# SAD_1_0.net
KiCad netlist of a schematic drawn in EAGLE
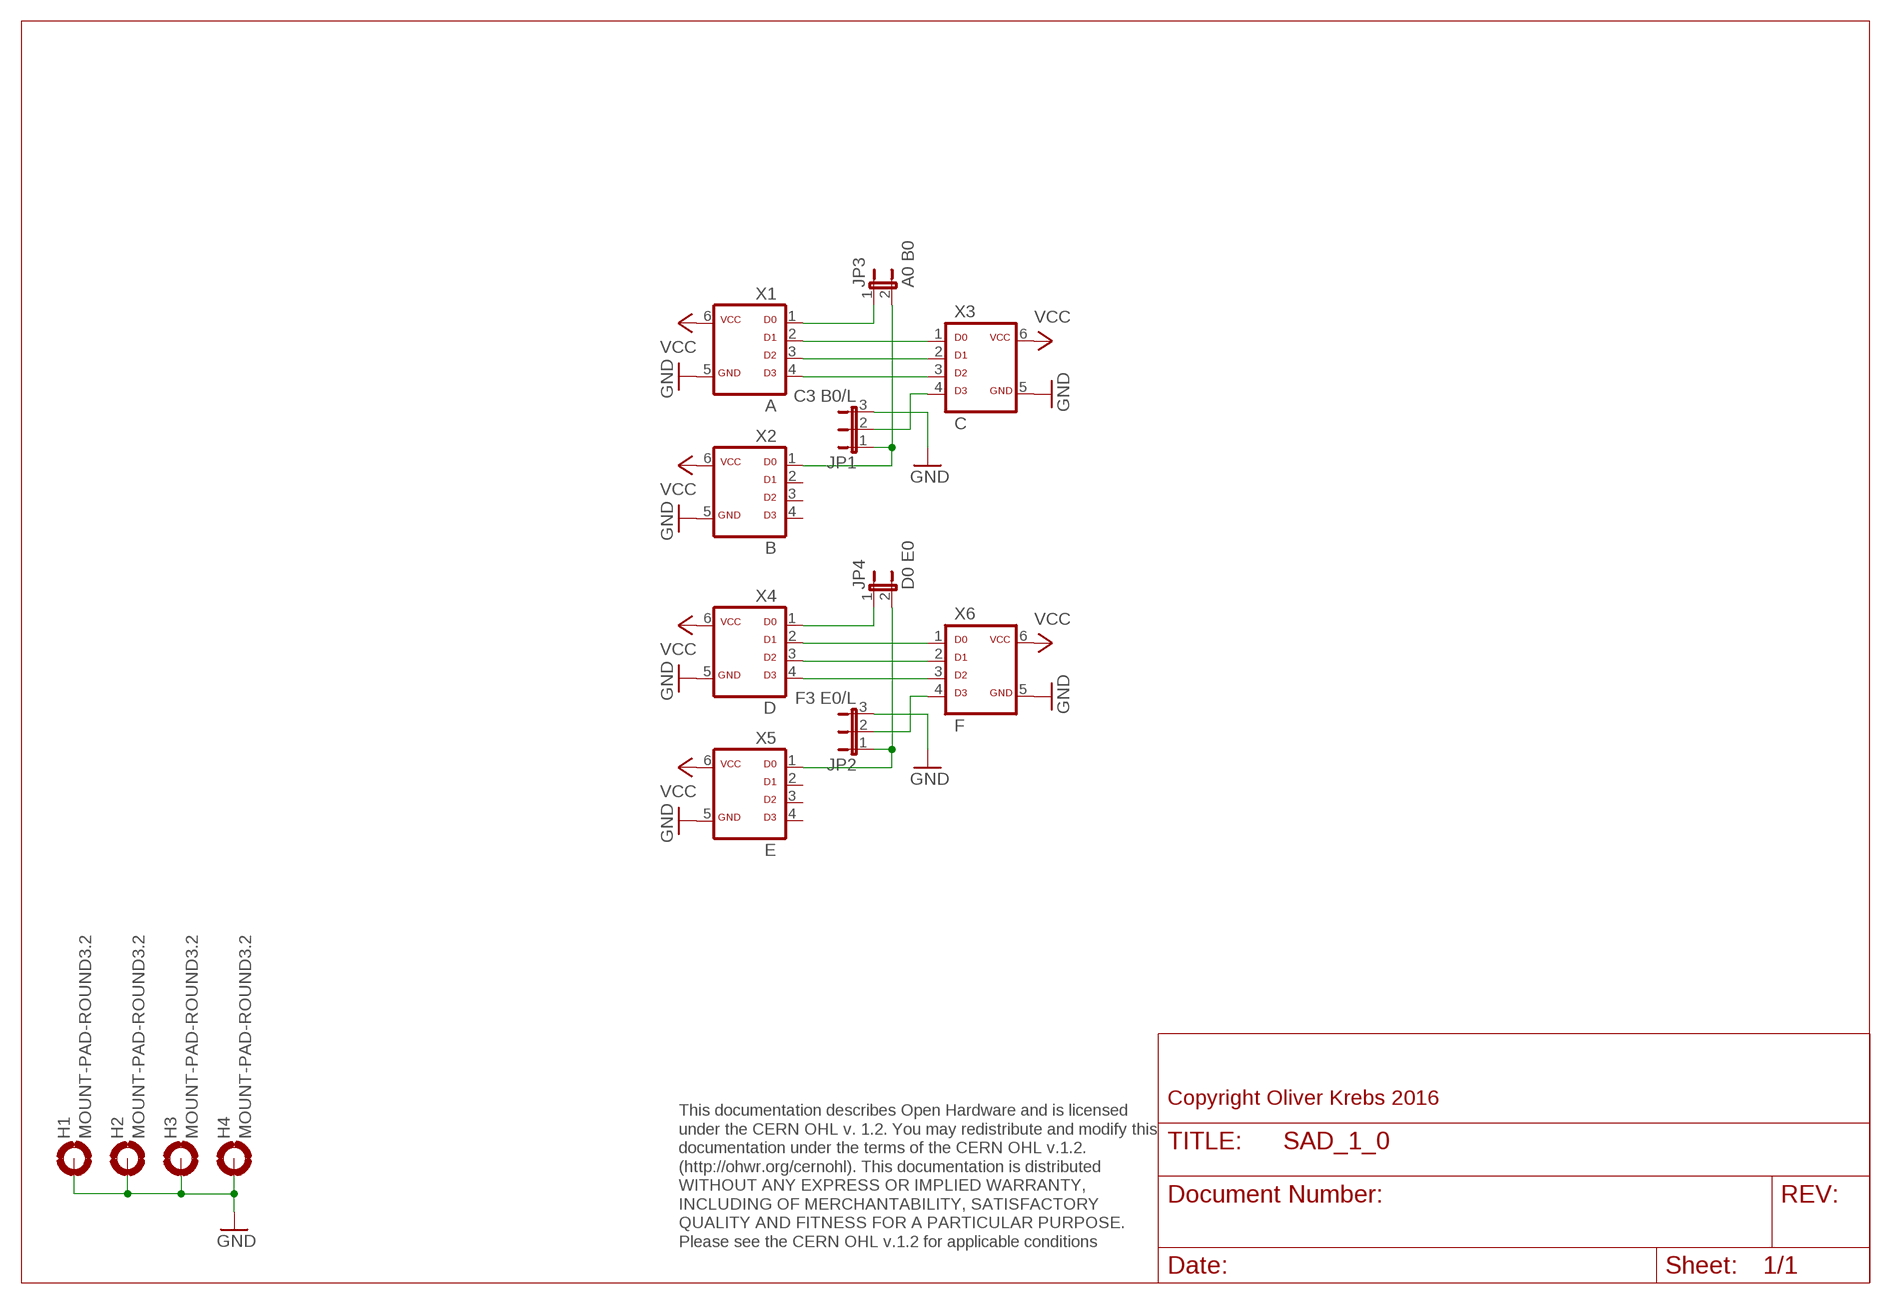
[diagram p0: schematic, sheet 1]

(export (version "E")
  (design (tool "Eeschema 10.0.6"))
  (components
    (comp (ref "H1")
      (value "MOUNT-PAD-ROUND3.2")
      (footprint "eagle-import:3,2-PAD")
      (libsource (lib "eagle-import") (part "MOUNT-PAD-ROUND3.2"))
    )
    (comp (ref "H2")
      (value "MOUNT-PAD-ROUND3.2")
      (footprint "eagle-import:3,2-PAD")
      (libsource (lib "eagle-import") (part "MOUNT-PAD-ROUND3.2"))
    )
    (comp (ref "H3")
      (value "MOUNT-PAD-ROUND3.2")
      (footprint "eagle-import:3,2-PAD")
      (libsource (lib "eagle-import") (part "MOUNT-PAD-ROUND3.2"))
    )
    (comp (ref "H4")
      (value "MOUNT-PAD-ROUND3.2")
      (footprint "eagle-import:3,2-PAD")
      (libsource (lib "eagle-import") (part "MOUNT-PAD-ROUND3.2"))
    )
    (comp (ref "JP1")
      (value "C3 B0/L")
      (footprint "eagle-import:JP2")
      (libsource (lib "eagle-import") (part "JP2E"))
    )
    (comp (ref "JP2")
      (value "F3 E0/L")
      (footprint "eagle-import:JP2")
      (libsource (lib "eagle-import") (part "JP2E"))
    )
    (comp (ref "JP3")
      (value "A0 B0")
      (footprint "eagle-import:JP1")
      (libsource (lib "eagle-import") (part "JP1E"))
    )
    (comp (ref "JP4")
      (value "D0 E0")
      (footprint "eagle-import:JP1")
      (libsource (lib "eagle-import") (part "JP1E"))
    )
    (comp (ref "X1")
      (value "A")
      (footprint "eagle-import:ML-6")
      (libsource (lib "eagle-import") (part "ML6D"))
    )
    (comp (ref "X2")
      (value "B")
      (footprint "eagle-import:ML-6")
      (libsource (lib "eagle-import") (part "ML6D"))
    )
    (comp (ref "X3")
      (value "C")
      (footprint "eagle-import:ML-6")
      (libsource (lib "eagle-import") (part "ML6D"))
    )
    (comp (ref "X4")
      (value "D")
      (footprint "eagle-import:ML-6")
      (libsource (lib "eagle-import") (part "ML6D"))
    )
    (comp (ref "X5")
      (value "E")
      (footprint "eagle-import:ML-6")
      (libsource (lib "eagle-import") (part "ML6D"))
    )
    (comp (ref "X6")
      (value "F")
      (footprint "eagle-import:ML-6")
      (libsource (lib "eagle-import") (part "ML6D"))
    )
  )
  (nets
    (net (code "1") (name "GND") (class "Default")
      (node (ref "H1") (pin "B3,2") (pinfunction "MOUNT_B3,2") (pintype "passive"))
      (node (ref "H2") (pin "B3,2") (pinfunction "MOUNT_B3,2") (pintype "passive"))
      (node (ref "H3") (pin "B3,2") (pinfunction "MOUNT_B3,2") (pintype "passive"))
      (node (ref "H4") (pin "B3,2") (pinfunction "MOUNT_B3,2") (pintype "passive"))
      (node (ref "JP1") (pin "3") (pinfunction "3_3") (pintype "passive"))
      (node (ref "JP2") (pin "3") (pinfunction "3_3") (pintype "passive"))
      (node (ref "X1") (pin "5") (pinfunction "5_5") (pintype "passive"))
      (node (ref "X2") (pin "5") (pinfunction "5_5") (pintype "passive"))
      (node (ref "X3") (pin "5") (pinfunction "5_5") (pintype "passive"))
      (node (ref "X4") (pin "5") (pinfunction "5_5") (pintype "passive"))
      (node (ref "X5") (pin "5") (pinfunction "5_5") (pintype "passive"))
      (node (ref "X6") (pin "5") (pinfunction "5_5") (pintype "passive"))
    )
    (net (code "2") (name "Net-(JP1-Pad1)") (class "Default")
      (node (ref "JP1") (pin "1") (pinfunction "1_1") (pintype "passive"))
      (node (ref "JP3") (pin "2") (pinfunction "2_2") (pintype "passive"))
      (node (ref "X2") (pin "1") (pinfunction "1_1") (pintype "passive"))
    )
    (net (code "3") (name "Net-(JP1-Pad2)") (class "Default")
      (node (ref "JP1") (pin "2") (pinfunction "2_2") (pintype "passive"))
      (node (ref "X3") (pin "4") (pinfunction "4_4") (pintype "passive"))
    )
    (net (code "4") (name "Net-(JP2-Pad1)") (class "Default")
      (node (ref "JP2") (pin "1") (pinfunction "1_1") (pintype "passive"))
      (node (ref "JP4") (pin "2") (pinfunction "2_2") (pintype "passive"))
      (node (ref "X5") (pin "1") (pinfunction "1_1") (pintype "passive"))
    )
    (net (code "5") (name "Net-(JP2-Pad2)") (class "Default")
      (node (ref "JP2") (pin "2") (pinfunction "2_2") (pintype "passive"))
      (node (ref "X6") (pin "4") (pinfunction "4_4") (pintype "passive"))
    )
    (net (code "6") (name "Net-(JP3-Pad1)") (class "Default")
      (node (ref "JP3") (pin "1") (pinfunction "1_1") (pintype "passive"))
      (node (ref "X1") (pin "1") (pinfunction "1_1") (pintype "passive"))
    )
    (net (code "7") (name "Net-(JP4-Pad1)") (class "Default")
      (node (ref "JP4") (pin "1") (pinfunction "1_1") (pintype "passive"))
      (node (ref "X4") (pin "1") (pinfunction "1_1") (pintype "passive"))
    )
    (net (code "8") (name "Net-(X1-Pad2)") (class "Default")
      (node (ref "X1") (pin "2") (pinfunction "2_2") (pintype "passive"))
      (node (ref "X3") (pin "1") (pinfunction "1_1") (pintype "passive"))
    )
    (net (code "9") (name "Net-(X1-Pad3)") (class "Default")
      (node (ref "X1") (pin "3") (pinfunction "3_3") (pintype "passive"))
      (node (ref "X3") (pin "2") (pinfunction "2_2") (pintype "passive"))
    )
    (net (code "10") (name "Net-(X1-Pad4)") (class "Default")
      (node (ref "X1") (pin "4") (pinfunction "4_4") (pintype "passive"))
      (node (ref "X3") (pin "3") (pinfunction "3_3") (pintype "passive"))
    )
    (net (code "11") (name "Net-(X4-Pad2)") (class "Default")
      (node (ref "X4") (pin "2") (pinfunction "2_2") (pintype "passive"))
      (node (ref "X6") (pin "1") (pinfunction "1_1") (pintype "passive"))
    )
    (net (code "12") (name "Net-(X4-Pad3)") (class "Default")
      (node (ref "X4") (pin "3") (pinfunction "3_3") (pintype "passive"))
      (node (ref "X6") (pin "2") (pinfunction "2_2") (pintype "passive"))
    )
    (net (code "13") (name "Net-(X4-Pad4)") (class "Default")
      (node (ref "X4") (pin "4") (pinfunction "4_4") (pintype "passive"))
      (node (ref "X6") (pin "3") (pinfunction "3_3") (pintype "passive"))
    )
    (net (code "14") (name "VCC") (class "Default")
      (node (ref "X1") (pin "6") (pinfunction "6_6") (pintype "passive"))
      (node (ref "X2") (pin "6") (pinfunction "6_6") (pintype "passive"))
      (node (ref "X3") (pin "6") (pinfunction "6_6") (pintype "passive"))
      (node (ref "X4") (pin "6") (pinfunction "6_6") (pintype "passive"))
      (node (ref "X5") (pin "6") (pinfunction "6_6") (pintype "passive"))
      (node (ref "X6") (pin "6") (pinfunction "6_6") (pintype "passive"))
    )
    (net (code "15") (name "unconnected-(X2-Pad2)") (class "Default")
      (node (ref "X2") (pin "2") (pinfunction "2_2") (pintype "passive"))
    )
    (net (code "16") (name "unconnected-(X2-Pad3)") (class "Default")
      (node (ref "X2") (pin "3") (pinfunction "3_3") (pintype "passive"))
    )
    (net (code "17") (name "unconnected-(X2-Pad4)") (class "Default")
      (node (ref "X2") (pin "4") (pinfunction "4_4") (pintype "passive"))
    )
    (net (code "18") (name "unconnected-(X5-Pad2)") (class "Default")
      (node (ref "X5") (pin "2") (pinfunction "2_2") (pintype "passive"))
    )
    (net (code "19") (name "unconnected-(X5-Pad3)") (class "Default")
      (node (ref "X5") (pin "3") (pinfunction "3_3") (pintype "passive"))
    )
    (net (code "20") (name "unconnected-(X5-Pad4)") (class "Default")
      (node (ref "X5") (pin "4") (pinfunction "4_4") (pintype "passive"))
    )
  )
)
